# OpAmp_NonInvertente_741xSHUNT-50A.net
KiCad netlist of a schematic drawn in EAGLE
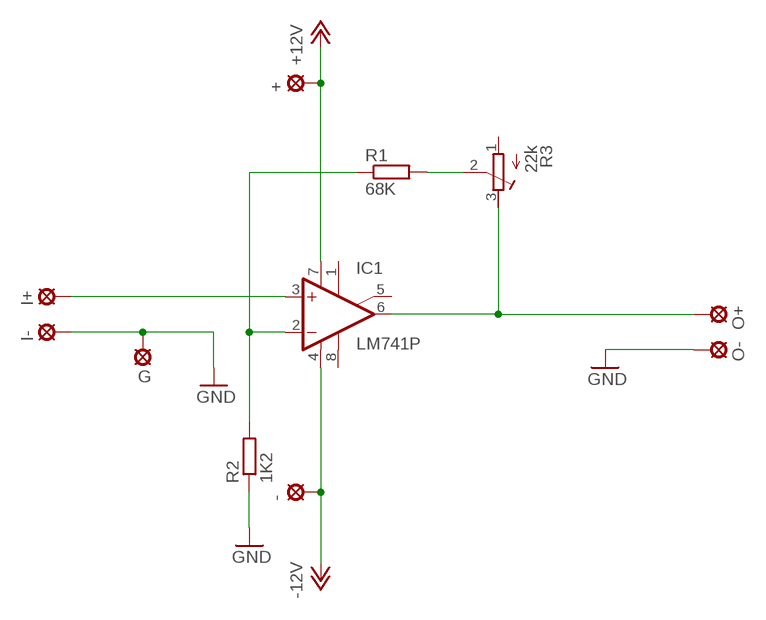
[diagram p0: schematic, sheet 1]

(export (version "E")
  (design (tool "Eeschema 10.0.6"))
  (components
    (comp (ref "+")
      (value "LSP10")
      (footprint "eagle-import:LSP10")
      (libsource (lib "eagle-import") (part "LSP10"))
    )
    (comp (ref "-")
      (value "LSP10")
      (footprint "eagle-import:LSP10")
      (libsource (lib "eagle-import") (part "LSP10"))
    )
    (comp (ref "G")
      (value "LSP10")
      (footprint "eagle-import:LSP10")
      (libsource (lib "eagle-import") (part "LSP10"))
    )
    (comp (ref "I+")
      (value "LSP10")
      (footprint "eagle-import:LSP10")
      (libsource (lib "eagle-import") (part "LSP10"))
    )
    (comp (ref "I-")
      (value "LSP10")
      (footprint "eagle-import:LSP10")
      (libsource (lib "eagle-import") (part "LSP10"))
    )
    (comp (ref "IC1")
      (value "LM741P")
      (footprint "eagle-import:DIL08")
      (libsource (lib "eagle-import") (part "741PLM"))
    )
    (comp (ref "O+")
      (value "LSP10")
      (footprint "eagle-import:LSP10")
      (libsource (lib "eagle-import") (part "LSP10"))
    )
    (comp (ref "O-")
      (value "LSP10")
      (footprint "eagle-import:LSP10")
      (libsource (lib "eagle-import") (part "LSP10"))
    )
    (comp (ref "R1")
      (value "68K")
      (footprint "eagle-import:0207_12")
      (libsource (lib "eagle-import") (part "R-EU_0207/12"))
    )
    (comp (ref "R2")
      (value "1K2")
      (footprint "eagle-import:0207_12")
      (libsource (lib "eagle-import") (part "R-EU_0207/12"))
    )
    (comp (ref "R3")
      (value "22k")
      (footprint "eagle-import:RTRIM3339P")
      (libsource (lib "eagle-import") (part "R-TRIMM3339P"))
    )
  )
  (nets
    (net (code "1") (name "+12V") (class "Default")
      (node (ref "+") (pin "MP") (pinfunction "MP_MP") (pintype "passive"))
      (node (ref "IC1") (pin "7") (pinfunction "V+_7") (pintype "power_in"))
    )
    (net (code "2") (name "-12V") (class "Default")
      (node (ref "-") (pin "MP") (pinfunction "MP_MP") (pintype "passive"))
      (node (ref "IC1") (pin "4") (pinfunction "V-_4") (pintype "power_in"))
    )
    (net (code "3") (name "GND") (class "Default")
      (node (ref "G") (pin "MP") (pinfunction "MP_MP") (pintype "passive"))
      (node (ref "I-") (pin "MP") (pinfunction "MP_MP") (pintype "passive"))
      (node (ref "O-") (pin "MP") (pinfunction "MP_MP") (pintype "passive"))
      (node (ref "R2") (pin "1") (pinfunction "1_1") (pintype "passive"))
    )
    (net (code "4") (name "Net-(IC1-+IN)") (class "Default")
      (node (ref "I+") (pin "MP") (pinfunction "MP_MP") (pintype "passive"))
      (node (ref "IC1") (pin "3") (pinfunction "+IN_3") (pintype "input"))
    )
    (net (code "5") (name "Net-(IC1--IN)") (class "Default")
      (node (ref "IC1") (pin "2") (pinfunction "-IN_2") (pintype "input"))
      (node (ref "R1") (pin "1") (pinfunction "1_1") (pintype "passive"))
      (node (ref "R2") (pin "2") (pinfunction "2_2") (pintype "passive"))
    )
    (net (code "6") (name "Net-(IC1-OUT)") (class "Default")
      (node (ref "IC1") (pin "6") (pinfunction "OUT_6") (pintype "output"))
      (node (ref "O+") (pin "MP") (pinfunction "MP_MP") (pintype "passive"))
      (node (ref "R3") (pin "3") (pinfunction "E_3") (pintype "passive"))
    )
    (net (code "7") (name "Net-(R3-S)") (class "Default")
      (node (ref "R1") (pin "2") (pinfunction "2_2") (pintype "passive"))
      (node (ref "R3") (pin "2") (pinfunction "S_2") (pintype "passive"))
    )
    (net (code "8") (name "unconnected-(IC1-ON1-Pad1)") (class "Default")
      (node (ref "IC1") (pin "1") (pinfunction "ON1_1") (pintype "passive"))
    )
    (net (code "9") (name "unconnected-(IC1-ON2-Pad5)") (class "Default")
      (node (ref "IC1") (pin "5") (pinfunction "ON2_5") (pintype "passive"))
    )
    (net (code "10") (name "unconnected-(IC1-OPT-Pad8)") (class "Default")
      (node (ref "IC1") (pin "8") (pinfunction "OPT_8") (pintype "passive"))
    )
    (net (code "11") (name "unconnected-(R3-A-Pad1)") (class "Default")
      (node (ref "R3") (pin "1") (pinfunction "A_1") (pintype "passive"))
    )
  )
)
